# charlie.net
KiCad netlist of a schematic drawn in EAGLE
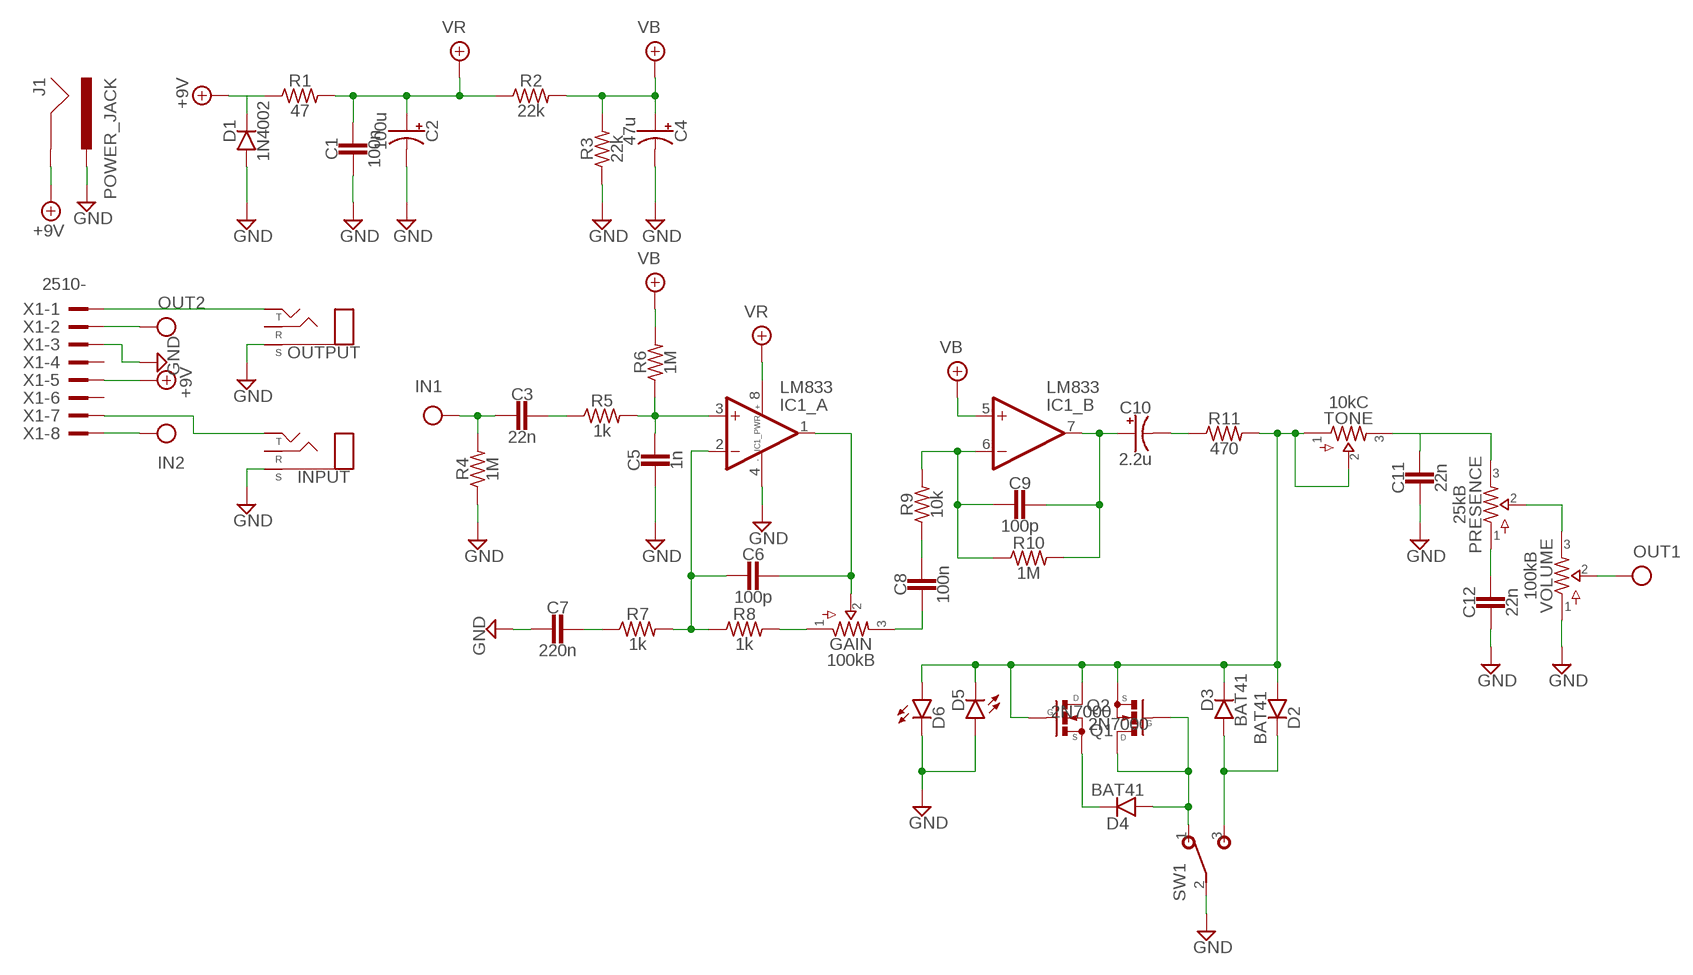
[diagram p0: schematic, sheet 1]

(export (version "E")
  (design (tool "Eeschema 10.0.6"))
  (components
    (comp (ref "C1")
      (value "100n")
      (footprint "eagle-import:050X030_025_2")
      (libsource (lib "eagle-import") (part "CER/FILM2"))
    )
    (comp (ref "C2")
      (value "100u")
      (footprint "eagle-import:050_020")
      (libsource (lib "eagle-import") (part "0500"))
    )
    (comp (ref "C3")
      (value "22n")
      (footprint "eagle-import:BOX_SMALL")
      (libsource (lib "eagle-import") (part "CER/FILMBOX.1"))
    )
    (comp (ref "C4")
      (value "47u")
      (footprint "eagle-import:050_020")
      (libsource (lib "eagle-import") (part "0500"))
    )
    (comp (ref "C5")
      (value "1n")
      (footprint "eagle-import:BOX_SMALL")
      (libsource (lib "eagle-import") (part "CER/FILMBOX.1"))
    )
    (comp (ref "C6")
      (value "100p")
      (footprint "eagle-import:050X030_025_2")
      (libsource (lib "eagle-import") (part "CER/FILM2"))
    )
    (comp (ref "C7")
      (value "220n")
      (footprint "eagle-import:BOX_SMALL")
      (libsource (lib "eagle-import") (part "CER/FILMBOX.1"))
    )
    (comp (ref "C8")
      (value "100n")
      (footprint "eagle-import:BOX_SMALL")
      (libsource (lib "eagle-import") (part "CER/FILMBOX.1"))
    )
    (comp (ref "C9")
      (value "100p")
      (footprint "eagle-import:050X030_025_2")
      (libsource (lib "eagle-import") (part "CER/FILM2"))
    )
    (comp (ref "C10")
      (value "2.2u")
      (footprint "eagle-import:050_020")
      (libsource (lib "eagle-import") (part "0500"))
    )
    (comp (ref "C11")
      (value "22n")
      (footprint "eagle-import:BOX_SMALL")
      (libsource (lib "eagle-import") (part "CER/FILMBOX.1"))
    )
    (comp (ref "C12")
      (value "22n")
      (footprint "eagle-import:BOX_SMALL")
      (libsource (lib "eagle-import") (part "CER/FILMBOX.1"))
    )
    (comp (ref "D1")
      (value "1N4002")
      (footprint "eagle-import:DO41-2")
      (libsource (lib "eagle-import") (part "DO41.2"))
    )
    (comp (ref "D2")
      (value "BAT41")
      (footprint "eagle-import:DO35-2")
      (libsource (lib "eagle-import") (part "DO35.2"))
    )
    (comp (ref "D3")
      (value "BAT41")
      (footprint "eagle-import:DO35-2")
      (libsource (lib "eagle-import") (part "DO35.2"))
    )
    (comp (ref "D4")
      (value "BAT41")
      (footprint "eagle-import:DO35-2")
      (libsource (lib "eagle-import") (part "DO35.2"))
    )
    (comp (ref "D5")
      (value "LED")
      (footprint "eagle-import:3MM_D")
      (libsource (lib "eagle-import") (part "LED"))
    )
    (comp (ref "D6")
      (value "LED")
      (footprint "eagle-import:3MM_D")
      (libsource (lib "eagle-import") (part "LED"))
    )
    (comp (ref "GAIN")
      (value "100kB")
      (footprint "eagle-import:16MM")
      (libsource (lib "eagle-import") (part "POTS16MM"))
    )
    (comp (ref "IC1")
      (value "LM833")
      (footprint "eagle-import:DIL08")
      (libsource (lib "eagle-import") (part "DUALTH"))
    )
    (comp (ref "INPUT")
      (value "STEREONMJ")
      (footprint "eagle-import:NMJ6HCD2")
      (libsource (lib "eagle-import") (part "STEREONMJ"))
    )
    (comp (ref "J1")
      (value "POWER_JACK")
      (footprint "eagle-import:POWER_JACK_PTH")
      (libsource (lib "eagle-import") (part "POWER_JACK"))
    )
    (comp (ref "OUTPUT")
      (value "STEREONMJ")
      (footprint "eagle-import:NMJ6HCD2")
      (libsource (lib "eagle-import") (part "STEREONMJ"))
    )
    (comp (ref "PRESENCE")
      (value "25kB")
      (footprint "eagle-import:16MM")
      (libsource (lib "eagle-import") (part "POTS16MM"))
    )
    (comp (ref "Q1")
      (value "2N7000")
      (footprint "eagle-import:TO92-")
      (libsource (lib "eagle-import") (part "2N7000"))
    )
    (comp (ref "Q2")
      (value "2N7000")
      (footprint "eagle-import:TO92-")
      (libsource (lib "eagle-import") (part "2N7000"))
    )
    (comp (ref "R1")
      (value "47")
      (footprint "eagle-import:R0207_3")
      (libsource (lib "eagle-import") (part "R_.3B"))
    )
    (comp (ref "R2")
      (value "22k")
      (footprint "eagle-import:R0207_3")
      (libsource (lib "eagle-import") (part "R_.3B"))
    )
    (comp (ref "R3")
      (value "22k")
      (footprint "eagle-import:R0207_3")
      (libsource (lib "eagle-import") (part "R_.3B"))
    )
    (comp (ref "R4")
      (value "1M")
      (footprint "eagle-import:R0207_3")
      (libsource (lib "eagle-import") (part "R_.3B"))
    )
    (comp (ref "R5")
      (value "1k")
      (footprint "eagle-import:R0207_3")
      (libsource (lib "eagle-import") (part "R_.3B"))
    )
    (comp (ref "R6")
      (value "1M")
      (footprint "eagle-import:R0207_3")
      (libsource (lib "eagle-import") (part "R_.3B"))
    )
    (comp (ref "R7")
      (value "1k")
      (footprint "eagle-import:R0207_3")
      (libsource (lib "eagle-import") (part "R_.3B"))
    )
    (comp (ref "R8")
      (value "1k")
      (footprint "eagle-import:R0207_3")
      (libsource (lib "eagle-import") (part "R_.3B"))
    )
    (comp (ref "R9")
      (value "10k")
      (footprint "eagle-import:R0207_3")
      (libsource (lib "eagle-import") (part "R_.3B"))
    )
    (comp (ref "R10")
      (value "1M")
      (footprint "eagle-import:R0207_3")
      (libsource (lib "eagle-import") (part "R_.3B"))
    )
    (comp (ref "R11")
      (value "470")
      (footprint "eagle-import:R0207_3")
      (libsource (lib "eagle-import") (part "R_.3B"))
    )
    (comp (ref "SW1")
      (value "SPDT")
      (footprint "eagle-import:M9040P")
      (libsource (lib "eagle-import") (part "SPDT"))
    )
    (comp (ref "TONE")
      (value "10kC")
      (footprint "eagle-import:16MM")
      (libsource (lib "eagle-import") (part "POTS16MM"))
    )
    (comp (ref "VOLUME")
      (value "100kB")
      (footprint "eagle-import:16MM")
      (libsource (lib "eagle-import") (part "POTS16MM"))
    )
    (comp (ref "X1")
      (value "2510-")
      (footprint "eagle-import:PAK100_2500-10")
      (fields (field (name "MF") "3M") (field (name "MPN") "2510-6002UB"))
      (libsource (lib "eagle-import") (part "2510-"))
    )
  )
  (nets
    (net (code "1") (name "+9V") (class "Default")
      (node (ref "D1") (pin "C") (pinfunction "C_C") (pintype "passive"))
      (node (ref "J1") (pin "GND") (pinfunction "GND_GND") (pintype "bidirectional"))
      (node (ref "R1") (pin "1") (pinfunction "1_1") (pintype "passive"))
      (node (ref "X1") (pin "5") (pinfunction "KL_5") (pintype "passive"))
    )
    (net (code "2") (name "GND") (class "Default")
      (node (ref "C1") (pin "2") (pinfunction "2_2") (pintype "passive"))
      (node (ref "C11") (pin "2") (pinfunction "2_2") (pintype "passive"))
      (node (ref "C12") (pin "2") (pinfunction "2_2") (pintype "passive"))
      (node (ref "C2") (pin "-") (pinfunction "-_-") (pintype "passive"))
      (node (ref "C4") (pin "-") (pinfunction "-_-") (pintype "passive"))
      (node (ref "C5") (pin "2") (pinfunction "2_2") (pintype "passive"))
      (node (ref "C7") (pin "2") (pinfunction "2_2") (pintype "passive"))
      (node (ref "D1") (pin "A") (pinfunction "A_A") (pintype "passive"))
      (node (ref "D5") (pin "ANODE") (pinfunction "A_ANODE") (pintype "passive"))
      (node (ref "D6") (pin "P$1") (pinfunction "C_P$1") (pintype "passive"))
      (node (ref "IC1") (pin "4") (pinfunction "V-_4") (pintype "power_in"))
      (node (ref "INPUT") (pin "S") (pinfunction "S_S") (pintype "passive"))
      (node (ref "J1") (pin "PWR") (pinfunction "PWR_PWR") (pintype "bidirectional"))
      (node (ref "OUTPUT") (pin "S") (pinfunction "S_S") (pintype "passive"))
      (node (ref "R3") (pin "1") (pinfunction "1_1") (pintype "passive"))
      (node (ref "R4") (pin "1") (pinfunction "1_1") (pintype "passive"))
      (node (ref "SW1") (pin "2") (pinfunction "P_2") (pintype "passive"))
      (node (ref "VOLUME") (pin "1") (pinfunction "1_1") (pintype "passive"))
      (node (ref "X1") (pin "3") (pinfunction "KL_3") (pintype "passive"))
    )
    (net (code "3") (name "IN") (class "Default")
      (node (ref "C3") (pin "2") (pinfunction "2_2") (pintype "passive"))
      (node (ref "R4") (pin "2") (pinfunction "2_2") (pintype "passive"))
      (node (ref "X1") (pin "8") (pinfunction "KL_8") (pintype "passive"))
    )
    (net (code "4") (name "Net-(C3-Pad1)") (class "Default")
      (node (ref "C3") (pin "1") (pinfunction "1_1") (pintype "passive"))
      (node (ref "R5") (pin "1") (pinfunction "1_1") (pintype "passive"))
    )
    (net (code "5") (name "Net-(C7-Pad1)") (class "Default")
      (node (ref "C7") (pin "1") (pinfunction "1_1") (pintype "passive"))
      (node (ref "R7") (pin "1") (pinfunction "1_1") (pintype "passive"))
    )
    (net (code "6") (name "Net-(C8-Pad1)") (class "Default")
      (node (ref "C8") (pin "1") (pinfunction "1_1") (pintype "passive"))
      (node (ref "R9") (pin "1") (pinfunction "1_1") (pintype "passive"))
    )
    (net (code "7") (name "Net-(C8-Pad2)") (class "Default")
      (node (ref "C8") (pin "2") (pinfunction "2_2") (pintype "passive"))
      (node (ref "GAIN") (pin "3") (pinfunction "3_3") (pintype "passive"))
    )
    (net (code "8") (name "Net-(C10-Pad-)") (class "Default")
      (node (ref "C10") (pin "-") (pinfunction "-_-") (pintype "passive"))
      (node (ref "R11") (pin "1") (pinfunction "1_1") (pintype "passive"))
    )
    (net (code "9") (name "Net-(C11-Pad1)") (class "Default")
      (node (ref "C11") (pin "1") (pinfunction "1_1") (pintype "passive"))
      (node (ref "PRESENCE") (pin "3") (pinfunction "3_3") (pintype "passive"))
      (node (ref "TONE") (pin "3") (pinfunction "3_3") (pintype "passive"))
    )
    (net (code "10") (name "Net-(C12-Pad1)") (class "Default")
      (node (ref "C12") (pin "1") (pinfunction "1_1") (pintype "passive"))
      (node (ref "PRESENCE") (pin "1") (pinfunction "1_1") (pintype "passive"))
    )
    (net (code "11") (name "Net-(D5-C)") (class "Default")
      (node (ref "D2") (pin "A") (pinfunction "A_A") (pintype "passive"))
      (node (ref "D3") (pin "C") (pinfunction "C_C") (pintype "passive"))
      (node (ref "D5") (pin "P$1") (pinfunction "C_P$1") (pintype "passive"))
      (node (ref "D6") (pin "ANODE") (pinfunction "A_ANODE") (pintype "passive"))
      (node (ref "Q1") (pin "3") (pinfunction "S_3") (pintype "passive"))
      (node (ref "Q2") (pin "1") (pinfunction "D_1") (pintype "passive"))
      (node (ref "Q2") (pin "2") (pinfunction "G_2") (pintype "passive"))
      (node (ref "R11") (pin "2") (pinfunction "2_2") (pintype "passive"))
      (node (ref "TONE") (pin "1") (pinfunction "1_1") (pintype "passive"))
      (node (ref "TONE") (pin "2") (pinfunction "2_2") (pintype "passive"))
    )
    (net (code "12") (name "Net-(GAIN-Pad1)") (class "Default")
      (node (ref "GAIN") (pin "1") (pinfunction "1_1") (pintype "passive"))
      (node (ref "R8") (pin "2") (pinfunction "2_2") (pintype "passive"))
    )
    (net (code "13") (name "Net-(IC1A-+IN)") (class "Default")
      (node (ref "C5") (pin "1") (pinfunction "1_1") (pintype "passive"))
      (node (ref "IC1") (pin "3") (pinfunction "+IN_3") (pintype "input"))
      (node (ref "R5") (pin "2") (pinfunction "2_2") (pintype "passive"))
      (node (ref "R6") (pin "1") (pinfunction "1_1") (pintype "passive"))
    )
    (net (code "14") (name "Net-(IC1A--IN)") (class "Default")
      (node (ref "C6") (pin "2") (pinfunction "2_2") (pintype "passive"))
      (node (ref "IC1") (pin "2") (pinfunction "-IN_2") (pintype "input"))
      (node (ref "R7") (pin "2") (pinfunction "2_2") (pintype "passive"))
      (node (ref "R8") (pin "1") (pinfunction "1_1") (pintype "passive"))
    )
    (net (code "15") (name "Net-(IC1A-OUT)") (class "Default")
      (node (ref "C6") (pin "1") (pinfunction "1_1") (pintype "passive"))
      (node (ref "GAIN") (pin "2") (pinfunction "2_2") (pintype "passive"))
      (node (ref "IC1") (pin "1") (pinfunction "OUT_1") (pintype "output"))
    )
    (net (code "16") (name "Net-(IC1B--IN)") (class "Default")
      (node (ref "C9") (pin "2") (pinfunction "2_2") (pintype "passive"))
      (node (ref "IC1") (pin "6") (pinfunction "-IN_6") (pintype "input"))
      (node (ref "R10") (pin "1") (pinfunction "1_1") (pintype "passive"))
      (node (ref "R9") (pin "2") (pinfunction "2_2") (pintype "passive"))
    )
    (net (code "17") (name "Net-(IC1B-OUT)") (class "Default")
      (node (ref "C10") (pin "+") (pinfunction "+_+") (pintype "passive"))
      (node (ref "C9") (pin "1") (pinfunction "1_1") (pintype "passive"))
      (node (ref "IC1") (pin "7") (pinfunction "OUT_7") (pintype "output"))
      (node (ref "R10") (pin "2") (pinfunction "2_2") (pintype "passive"))
    )
    (net (code "18") (name "Net-(PRESENCE-Pad2)") (class "Default")
      (node (ref "PRESENCE") (pin "2") (pinfunction "2_2") (pintype "passive"))
      (node (ref "VOLUME") (pin "3") (pinfunction "3_3") (pintype "passive"))
    )
    (net (code "19") (name "Net-(Q1-D)") (class "Default")
      (node (ref "D4") (pin "A") (pinfunction "A_A") (pintype "passive"))
      (node (ref "Q1") (pin "1") (pinfunction "D_1") (pintype "passive"))
      (node (ref "Q1") (pin "2") (pinfunction "G_2") (pintype "passive"))
      (node (ref "SW1") (pin "1") (pinfunction "O_1") (pintype "passive"))
    )
    (net (code "20") (name "Net-(Q2-S)") (class "Default")
      (node (ref "D4") (pin "C") (pinfunction "C_C") (pintype "passive"))
      (node (ref "Q2") (pin "3") (pinfunction "S_3") (pintype "passive"))
    )
    (net (code "21") (name "Net-(SW1-S)") (class "Default")
      (node (ref "D2") (pin "C") (pinfunction "C_C") (pintype "passive"))
      (node (ref "D3") (pin "A") (pinfunction "A_A") (pintype "passive"))
      (node (ref "SW1") (pin "3") (pinfunction "S_3") (pintype "passive"))
    )
    (net (code "22") (name "Net-(X1A-KL)") (class "Default")
      (node (ref "OUTPUT") (pin "T") (pinfunction "T_T") (pintype "passive"))
      (node (ref "X1") (pin "1") (pinfunction "KL_1") (pintype "passive"))
    )
    (net (code "23") (name "Net-(X1G-KL)") (class "Default")
      (node (ref "INPUT") (pin "T") (pinfunction "T_T") (pintype "passive"))
      (node (ref "X1") (pin "7") (pinfunction "KL_7") (pintype "passive"))
    )
    (net (code "24") (name "OUT") (class "Default")
      (node (ref "VOLUME") (pin "2") (pinfunction "2_2") (pintype "passive"))
      (node (ref "X1") (pin "2") (pinfunction "KL_2") (pintype "passive"))
    )
    (net (code "25") (name "VB") (class "Default")
      (node (ref "C4") (pin "+") (pinfunction "+_+") (pintype "passive"))
      (node (ref "IC1") (pin "5") (pinfunction "+IN_5") (pintype "input"))
      (node (ref "R2") (pin "2") (pinfunction "2_2") (pintype "passive"))
      (node (ref "R3") (pin "2") (pinfunction "2_2") (pintype "passive"))
      (node (ref "R6") (pin "2") (pinfunction "2_2") (pintype "passive"))
    )
    (net (code "26") (name "VR") (class "Default")
      (node (ref "C1") (pin "1") (pinfunction "1_1") (pintype "passive"))
      (node (ref "C2") (pin "+") (pinfunction "+_+") (pintype "passive"))
      (node (ref "IC1") (pin "8") (pinfunction "V+_8") (pintype "power_in"))
      (node (ref "R1") (pin "2") (pinfunction "2_2") (pintype "passive"))
      (node (ref "R2") (pin "1") (pinfunction "1_1") (pintype "passive"))
    )
    (net (code "27") (name "unconnected-(INPUT-PadR)") (class "Default")
      (node (ref "INPUT") (pin "R") (pinfunction "R_R") (pintype "passive"))
    )
    (net (code "28") (name "unconnected-(OUTPUT-PadR)") (class "Default")
      (node (ref "OUTPUT") (pin "R") (pinfunction "R_R") (pintype "passive"))
    )
    (net (code "29") (name "unconnected-(X1D-KL-Pad4)") (class "Default")
      (node (ref "X1") (pin "4") (pinfunction "KL_4") (pintype "passive"))
    )
    (net (code "30") (name "unconnected-(X1F-KL-Pad6)") (class "Default")
      (node (ref "X1") (pin "6") (pinfunction "KL_6") (pintype "passive"))
    )
  )
)
